# Ethernet-PHY.net
KiCad netlist of a schematic drawn in Altium Designer
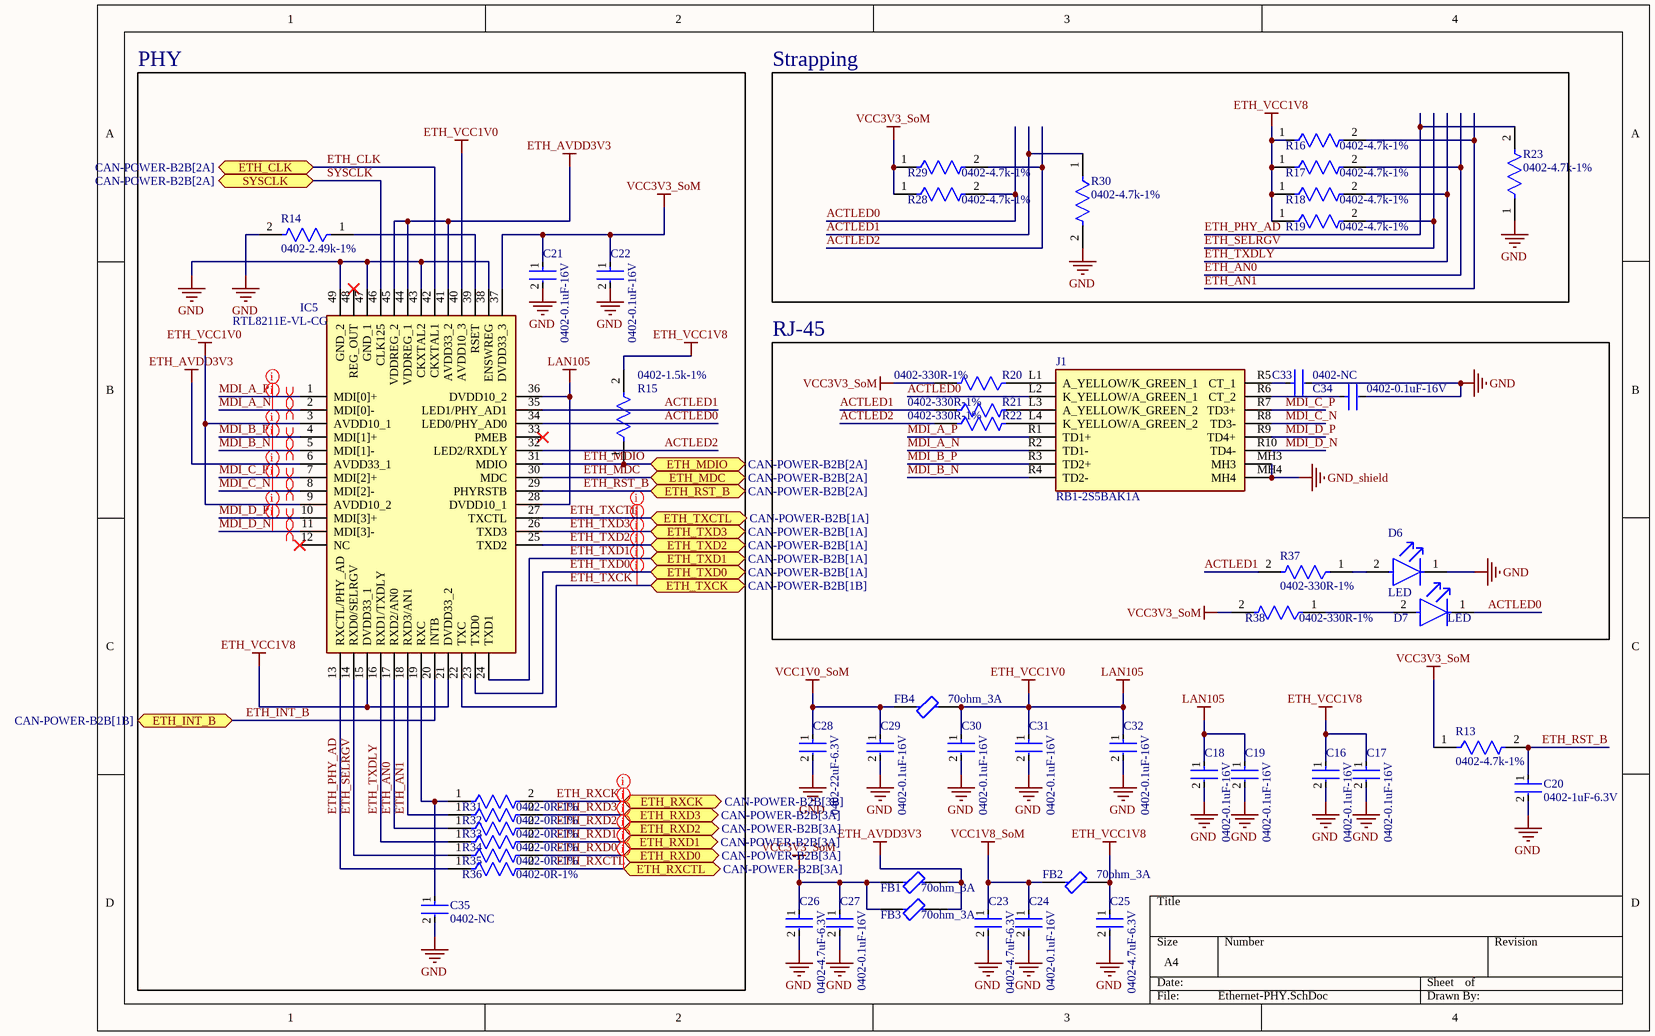
[diagram p0: Ethernet-PHY.SchDoc]

(export (version "E")
  (design (tool "Eeschema 10.0.6"))
  (components
    (comp (ref "C16")
      (value "0402-0.1uF-16V")
      (footprint "FP-GRM155-0_05-IPC_A")
      (description "CAP CER 0.22UF 10V X5R 0402")
      (fields (field (name "VOLTAGE") "10V") (field (name "TOLERANCE") "10%"))
      (libsource (lib "Altium Content Vault") (part "02cd4be3c70576c341d710602a673aa"))
    )
    (comp (ref "C17")
      (value "0402-0.1uF-16V")
      (footprint "FP-GRM155-0_05-IPC_A")
      (description "CAP CER 0.22UF 10V X5R 0402")
      (fields (field (name "VOLTAGE") "10V") (field (name "TOLERANCE") "10%"))
      (libsource (lib "Altium Content Vault") (part "02cd4be3c70576c341d710602a673aa"))
    )
    (comp (ref "C18")
      (value "0402-0.1uF-16V")
      (footprint "FP-GRM155-0_05-IPC_A")
      (description "CAP CER 0.22UF 10V X5R 0402")
      (fields (field (name "VOLTAGE") "10V") (field (name "TOLERANCE") "10%"))
      (libsource (lib "Altium Content Vault") (part "02cd4be3c70576c341d710602a673aa"))
    )
    (comp (ref "C19")
      (value "0402-0.1uF-16V")
      (footprint "FP-GRM155-0_05-IPC_A")
      (description "CAP CER 0.22UF 10V X5R 0402")
      (fields (field (name "VOLTAGE") "10V") (field (name "TOLERANCE") "10%"))
      (libsource (lib "Altium Content Vault") (part "02cd4be3c70576c341d710602a673aa"))
    )
    (comp (ref "C20")
      (value "0402-1uF-6.3V")
      (footprint "FP-GRM155-0_05-IPC_A")
      (description "CAP CER 0.22UF 10V X5R 0402")
      (fields (field (name "VOLTAGE") "10V") (field (name "TOLERANCE") "10%"))
      (libsource (lib "Altium Content Vault") (part "02cd4be3c70576c341d710602a673aa"))
    )
    (comp (ref "C21")
      (value "0402-0.1uF-16V")
      (footprint "FP-GRM155-0_05-IPC_A")
      (description "CAP CER 0.22UF 10V X5R 0402")
      (fields (field (name "VOLTAGE") "10V") (field (name "TOLERANCE") "10%"))
      (libsource (lib "Altium Content Vault") (part "02cd4be3c70576c341d710602a673aa"))
    )
    (comp (ref "C22")
      (value "0402-0.1uF-16V")
      (footprint "FP-GRM155-0_05-IPC_A")
      (description "CAP CER 0.22UF 10V X5R 0402")
      (fields (field (name "VOLTAGE") "10V") (field (name "TOLERANCE") "10%"))
      (libsource (lib "Altium Content Vault") (part "02cd4be3c70576c341d710602a673aa"))
    )
    (comp (ref "C23")
      (value "0402-4.7uF-6.3V")
      (footprint "FP-GRM155-0_05-IPC_A")
      (description "CAP CER 0.22UF 10V X5R 0402")
      (fields (field (name "VOLTAGE") "10V") (field (name "TOLERANCE") "10%"))
      (libsource (lib "Altium Content Vault") (part "02cd4be3c70576c341d710602a673aa"))
    )
    (comp (ref "C24")
      (value "0402-0.1uF-16V")
      (footprint "FP-GRM155-0_05-IPC_A")
      (description "CAP CER 0.22UF 10V X5R 0402")
      (fields (field (name "VOLTAGE") "10V") (field (name "TOLERANCE") "10%"))
      (libsource (lib "Altium Content Vault") (part "02cd4be3c70576c341d710602a673aa"))
    )
    (comp (ref "C25")
      (value "0402-4.7uF-6.3V")
      (footprint "FP-GRM155-0_05-IPC_A")
      (description "CAP CER 0.22UF 10V X5R 0402")
      (fields (field (name "VOLTAGE") "10V") (field (name "TOLERANCE") "10%"))
      (libsource (lib "Altium Content Vault") (part "02cd4be3c70576c341d710602a673aa"))
    )
    (comp (ref "C26")
      (value "0402-4.7uF-6.3V")
      (footprint "FP-GRM155-0_05-IPC_A")
      (description "CAP CER 0.22UF 10V X5R 0402")
      (fields (field (name "VOLTAGE") "10V") (field (name "TOLERANCE") "10%"))
      (libsource (lib "Altium Content Vault") (part "02cd4be3c70576c341d710602a673aa"))
    )
    (comp (ref "C27")
      (value "0402-0.1uF-16V")
      (footprint "FP-GRM155-0_05-IPC_A")
      (description "CAP CER 0.22UF 10V X5R 0402")
      (fields (field (name "VOLTAGE") "10V") (field (name "TOLERANCE") "10%"))
      (libsource (lib "Altium Content Vault") (part "02cd4be3c70576c341d710602a673aa"))
    )
    (comp (ref "C28")
      (value "0402-22uF-6.3V")
      (footprint "FP-GRM155-0_05-IPC_A")
      (description "CAP CER 0.22UF 10V X5R 0402")
      (fields (field (name "VOLTAGE") "10V") (field (name "TOLERANCE") "10%"))
      (libsource (lib "Altium Content Vault") (part "02cd4be3c70576c341d710602a673aa"))
    )
    (comp (ref "C29")
      (value "0402-0.1uF-16V")
      (footprint "FP-GRM155-0_05-IPC_A")
      (description "CAP CER 0.22UF 10V X5R 0402")
      (fields (field (name "VOLTAGE") "10V") (field (name "TOLERANCE") "10%"))
      (libsource (lib "Altium Content Vault") (part "02cd4be3c70576c341d710602a673aa"))
    )
    (comp (ref "C30")
      (value "0402-0.1uF-16V")
      (footprint "FP-GRM155-0_05-IPC_A")
      (description "CAP CER 0.22UF 10V X5R 0402")
      (fields (field (name "VOLTAGE") "10V") (field (name "TOLERANCE") "10%"))
      (libsource (lib "Altium Content Vault") (part "02cd4be3c70576c341d710602a673aa"))
    )
    (comp (ref "C31")
      (value "0402-0.1uF-16V")
      (footprint "FP-GRM155-0_05-IPC_A")
      (description "CAP CER 0.22UF 10V X5R 0402")
      (fields (field (name "VOLTAGE") "10V") (field (name "TOLERANCE") "10%"))
      (libsource (lib "Altium Content Vault") (part "02cd4be3c70576c341d710602a673aa"))
    )
    (comp (ref "C32")
      (value "0402-0.1uF-16V")
      (footprint "FP-GRM155-0_05-IPC_A")
      (description "CAP CER 0.22UF 10V X5R 0402")
      (fields (field (name "VOLTAGE") "10V") (field (name "TOLERANCE") "10%"))
      (libsource (lib "Altium Content Vault") (part "02cd4be3c70576c341d710602a673aa"))
    )
    (comp (ref "C33")
      (value "0402-NC")
      (footprint "FP-GRM155-0_05-IPC_A")
      (description "CAP CER 0.22UF 10V X5R 0402")
      (fields (field (name "VOLTAGE") "10V") (field (name "TOLERANCE") "10%"))
      (libsource (lib "") (part "02cd4be3c70576c341d710602a673aa_1"))
    )
    (comp (ref "C34")
      (value "0402-0.1uF-16V")
      (footprint "FP-GRM155-0_05-IPC_A")
      (description "CAP CER 0.22UF 10V X5R 0402")
      (fields (field (name "VOLTAGE") "10V") (field (name "TOLERANCE") "10%"))
      (libsource (lib "") (part "02cd4be3c70576c341d710602a673aa_1"))
    )
    (comp (ref "C35")
      (value "0402-NC")
      (footprint "FP-GRM155-0_05-IPC_A")
      (description "CAP CER 0.22UF 10V X5R 0402")
      (fields (field (name "VOLTAGE") "10V") (field (name "TOLERANCE") "10%"))
      (libsource (lib "Altium Content Vault") (part "02cd4be3c70576c341d710602a673aa"))
    )
    (comp (ref "D6")
      (value "LED")
      (footprint "FP-APHHS1005CGCK-MFG")
      (description "LED GREEN CLEAR CHIP SMD")
      (libsource (lib "Altium Content Vault") (part "8706943c75ba83719d021d2fdc84c58"))
    )
    (comp (ref "D7")
      (value "LED")
      (footprint "FP-APHHS1005CGCK-MFG")
      (description "LED GREEN CLEAR CHIP SMD")
      (libsource (lib "Altium Content Vault") (part "8706943c75ba83719d021d2fdc84c58"))
    )
    (comp (ref "FB1")
      (value "70ohm_3A")
      (footprint "FP-MPZ2012-MFG")
      (description "FERRITE BEAD 220 OHM 0805 1LN")
      (fields (field (name "TOLERANCE") "25%"))
      (libsource (lib "Altium Content Vault") (part "5f30dd21d616792df468990f7003faa"))
    )
    (comp (ref "FB2")
      (value "70ohm_3A")
      (footprint "FP-MPZ2012-MFG")
      (description "FERRITE BEAD 220 OHM 0805 1LN")
      (fields (field (name "TOLERANCE") "25%"))
      (libsource (lib "Altium Content Vault") (part "5f30dd21d616792df468990f7003faa"))
    )
    (comp (ref "FB3")
      (value "70ohm_3A")
      (footprint "FP-MPZ2012-MFG")
      (description "FERRITE BEAD 220 OHM 0805 1LN")
      (fields (field (name "TOLERANCE") "25%"))
      (libsource (lib "Altium Content Vault") (part "5f30dd21d616792df468990f7003faa"))
    )
    (comp (ref "FB4")
      (value "70ohm_3A")
      (footprint "FP-MPZ2012-MFG")
      (description "FERRITE BEAD 220 OHM 0805 1LN")
      (fields (field (name "TOLERANCE") "25%"))
      (libsource (lib "Altium Content Vault") (part "5f30dd21d616792df468990f7003faa"))
    )
    (comp (ref "IC5")
      (value "RTL8211E-VL-CG")
      (footprint "SamacSys:QFN40P600X600X100-49N")
      (description "Integrated Circuit")
      (libsource (lib "*") (part "RTL8211E-VL-CG"))
    )
    (comp (ref "J1")
      (value "RB1-2S5BAK1A")
      (footprint "SamacSys:RB12S5BAK1A")
      (description "Connector")
      (libsource (lib "*") (part "RB1-2S5BAK1A"))
    )
    (comp (ref "R13")
      (value "0402-4.7k-1%")
      (footprint "FP-CRCW0402-e3-IPC_C")
      (description "RES Thick Film, 0Ω, 0.063W, 0402")
      (fields (field (name "TOLERANCE") "5%"))
      (libsource (lib "Altium Content Vault") (part "1029c3af85768c4190bb7ad29bc67b5"))
    )
    (comp (ref "R14")
      (value "0402-2.49k-1%")
      (footprint "FP-CRCW0402-e3-IPC_C")
      (description "RES Thick Film, 0Ω, 0.063W, 0402")
      (fields (field (name "TOLERANCE") "5%"))
      (libsource (lib "Altium Content Vault") (part "1029c3af85768c4190bb7ad29bc67b5"))
    )
    (comp (ref "R15")
      (value "0402-1.5k-1%")
      (footprint "FP-CRCW0402-e3-IPC_C")
      (description "RES Thick Film, 0Ω, 0.063W, 0402")
      (fields (field (name "TOLERANCE") "5%"))
      (libsource (lib "Altium Content Vault") (part "1029c3af85768c4190bb7ad29bc67b5"))
    )
    (comp (ref "R16")
      (value "0402-4.7k-1%")
      (footprint "FP-CRCW0402-e3-IPC_C")
      (description "RES Thick Film, 0Ω, 0.063W, 0402")
      (fields (field (name "TOLERANCE") "5%"))
      (libsource (lib "Altium Content Vault") (part "1029c3af85768c4190bb7ad29bc67b5"))
    )
    (comp (ref "R17")
      (value "0402-4.7k-1%")
      (footprint "FP-CRCW0402-e3-IPC_C")
      (description "RES Thick Film, 0Ω, 0.063W, 0402")
      (fields (field (name "TOLERANCE") "5%"))
      (libsource (lib "Altium Content Vault") (part "1029c3af85768c4190bb7ad29bc67b5"))
    )
    (comp (ref "R18")
      (value "0402-4.7k-1%")
      (footprint "FP-CRCW0402-e3-IPC_C")
      (description "RES Thick Film, 0Ω, 0.063W, 0402")
      (fields (field (name "TOLERANCE") "5%"))
      (libsource (lib "Altium Content Vault") (part "1029c3af85768c4190bb7ad29bc67b5"))
    )
    (comp (ref "R19")
      (value "0402-4.7k-1%")
      (footprint "FP-CRCW0402-e3-IPC_C")
      (description "RES Thick Film, 0Ω, 0.063W, 0402")
      (fields (field (name "TOLERANCE") "5%"))
      (libsource (lib "Altium Content Vault") (part "1029c3af85768c4190bb7ad29bc67b5"))
    )
    (comp (ref "R20")
      (value "0402-330R-1%")
      (footprint "FP-CRCW0402-e3-IPC_C")
      (description "RES Thick Film, 0Ω, 0.063W, 0402")
      (fields (field (name "TOLERANCE") "5%"))
      (libsource (lib "") (part "1029c3af85768c4190bb7ad29bc67b5_1"))
    )
    (comp (ref "R21")
      (value "0402-330R-1%")
      (footprint "FP-CRCW0402-e3-IPC_C")
      (description "RES Thick Film, 0Ω, 0.063W, 0402")
      (fields (field (name "TOLERANCE") "5%"))
      (libsource (lib "") (part "1029c3af85768c4190bb7ad29bc67b5_1"))
    )
    (comp (ref "R22")
      (value "0402-330R-1%")
      (footprint "FP-CRCW0402-e3-IPC_C")
      (description "RES Thick Film, 0Ω, 0.063W, 0402")
      (fields (field (name "TOLERANCE") "5%"))
      (libsource (lib "") (part "1029c3af85768c4190bb7ad29bc67b5_1"))
    )
    (comp (ref "R23")
      (value "0402-4.7k-1%")
      (footprint "FP-CRCW0402-e3-IPC_C")
      (description "RES Thick Film, 0Ω, 0.063W, 0402")
      (fields (field (name "TOLERANCE") "5%"))
      (libsource (lib "Altium Content Vault") (part "1029c3af85768c4190bb7ad29bc67b5"))
    )
    (comp (ref "R28")
      (value "0402-4.7k-1%")
      (footprint "FP-CRCW0402-e3-IPC_C")
      (description "RES Thick Film, 0Ω, 0.063W, 0402")
      (fields (field (name "TOLERANCE") "5%"))
      (libsource (lib "Altium Content Vault") (part "1029c3af85768c4190bb7ad29bc67b5"))
    )
    (comp (ref "R29")
      (value "0402-4.7k-1%")
      (footprint "FP-CRCW0402-e3-IPC_C")
      (description "RES Thick Film, 0Ω, 0.063W, 0402")
      (fields (field (name "TOLERANCE") "5%"))
      (libsource (lib "Altium Content Vault") (part "1029c3af85768c4190bb7ad29bc67b5"))
    )
    (comp (ref "R30")
      (value "0402-4.7k-1%")
      (footprint "FP-CRCW0402-e3-IPC_C")
      (description "RES Thick Film, 0Ω, 0.063W, 0402")
      (fields (field (name "TOLERANCE") "5%"))
      (libsource (lib "Altium Content Vault") (part "1029c3af85768c4190bb7ad29bc67b5"))
    )
    (comp (ref "R31")
      (value "0402-0R-1%")
      (footprint "FP-CRCW0402-e3-IPC_C")
      (description "RES Thick Film, 0Ω, 0.063W, 0402")
      (fields (field (name "TOLERANCE") "5%"))
      (libsource (lib "Altium Content Vault") (part "1029c3af85768c4190bb7ad29bc67b5"))
    )
    (comp (ref "R32")
      (value "0402-0R-1%")
      (footprint "FP-CRCW0402-e3-IPC_C")
      (description "RES Thick Film, 0Ω, 0.063W, 0402")
      (fields (field (name "TOLERANCE") "5%"))
      (libsource (lib "Altium Content Vault") (part "1029c3af85768c4190bb7ad29bc67b5"))
    )
    (comp (ref "R33")
      (value "0402-0R-1%")
      (footprint "FP-CRCW0402-e3-IPC_C")
      (description "RES Thick Film, 0Ω, 0.063W, 0402")
      (fields (field (name "TOLERANCE") "5%"))
      (libsource (lib "Altium Content Vault") (part "1029c3af85768c4190bb7ad29bc67b5"))
    )
    (comp (ref "R34")
      (value "0402-0R-1%")
      (footprint "FP-CRCW0402-e3-IPC_C")
      (description "RES Thick Film, 0Ω, 0.063W, 0402")
      (fields (field (name "TOLERANCE") "5%"))
      (libsource (lib "Altium Content Vault") (part "1029c3af85768c4190bb7ad29bc67b5"))
    )
    (comp (ref "R35")
      (value "0402-0R-1%")
      (footprint "FP-CRCW0402-e3-IPC_C")
      (description "RES Thick Film, 0Ω, 0.063W, 0402")
      (fields (field (name "TOLERANCE") "5%"))
      (libsource (lib "Altium Content Vault") (part "1029c3af85768c4190bb7ad29bc67b5"))
    )
    (comp (ref "R36")
      (value "0402-0R-1%")
      (footprint "FP-CRCW0402-e3-IPC_C")
      (description "RES Thick Film, 0Ω, 0.063W, 0402")
      (fields (field (name "TOLERANCE") "5%"))
      (libsource (lib "Altium Content Vault") (part "1029c3af85768c4190bb7ad29bc67b5"))
    )
    (comp (ref "R37")
      (value "0402-330R-1%")
      (footprint "FP-CRCW0402-e3-IPC_C")
      (description "RES Thick Film, 0Ω, 0.063W, 0402")
      (fields (field (name "TOLERANCE") "5%"))
      (libsource (lib "Altium Content Vault") (part "1029c3af85768c4190bb7ad29bc67b5"))
    )
    (comp (ref "R38")
      (value "0402-330R-1%")
      (footprint "FP-CRCW0402-e3-IPC_C")
      (description "RES Thick Film, 0Ω, 0.063W, 0402")
      (fields (field (name "TOLERANCE") "5%"))
      (libsource (lib "Altium Content Vault") (part "1029c3af85768c4190bb7ad29bc67b5"))
    )
  )
  (nets
    (net (code "1") (name "/ACTLED0") (class "Default")
      (node (ref "D7") (pin "1") (pinfunction "C_1") (pintype "passive"))
      (node (ref "IC5") (pin "34") (pinfunction "LED0/PHY_AD0_34") (pintype "passive"))
      (node (ref "J1") (pin "L2") (pinfunction "K_YELLOW/A_GREEN_1_L2") (pintype "passive"))
      (node (ref "R28") (pin "2") (pinfunction "2_2") (pintype "passive"))
    )
    (net (code "2") (name "/ACTLED1") (class "Default")
      (node (ref "IC5") (pin "35") (pinfunction "LED1/PHY_AD1_35") (pintype "passive"))
      (node (ref "R21") (pin "1") (pinfunction "1_1") (pintype "passive"))
      (node (ref "R30") (pin "1") (pinfunction "1_1") (pintype "passive"))
      (node (ref "R37") (pin "2") (pinfunction "2_2") (pintype "passive"))
    )
    (net (code "3") (name "/ACTLED2") (class "Default")
      (node (ref "IC5") (pin "32") (pinfunction "LED2/RXDLY_32") (pintype "passive"))
      (node (ref "R22") (pin "1") (pinfunction "1_1") (pintype "passive"))
      (node (ref "R29") (pin "2") (pinfunction "2_2") (pintype "passive"))
    )
    (net (code "4") (name "/ETH_AN0") (class "Default")
      (node (ref "IC5") (pin "17") (pinfunction "RXD2/AN0_17") (pintype "passive"))
      (node (ref "R17") (pin "2") (pinfunction "2_2") (pintype "passive"))
      (node (ref "R33") (pin "1") (pinfunction "1_1") (pintype "passive"))
    )
    (net (code "5") (name "/ETH_AN1") (class "Default")
      (node (ref "IC5") (pin "18") (pinfunction "RXD3/AN1_18") (pintype "passive"))
      (node (ref "R16") (pin "2") (pinfunction "2_2") (pintype "passive"))
      (node (ref "R32") (pin "1") (pinfunction "1_1") (pintype "passive"))
    )
    (net (code "6") (name "/ETH_CLK") (class "Default")
      (node (ref "IC5") (pin "42") (pinfunction "CKXTAL1_42") (pintype "passive"))
    )
    (net (code "7") (name "/ETH_INT_B") (class "Default")
      (node (ref "IC5") (pin "20") (pinfunction "INTB_20") (pintype "passive"))
    )
    (net (code "8") (name "/ETH_MDC") (class "Default")
      (node (ref "IC5") (pin "30") (pinfunction "MDC_30") (pintype "passive"))
    )
    (net (code "9") (name "/ETH_MDIO") (class "Default")
      (node (ref "IC5") (pin "31") (pinfunction "MDIO_31") (pintype "passive"))
      (node (ref "R15") (pin "1") (pinfunction "1_1") (pintype "passive"))
    )
    (net (code "10") (name "/ETH_PHY_AD") (class "Default")
      (node (ref "IC5") (pin "13") (pinfunction "RXCTL/PHY_AD_13") (pintype "passive"))
      (node (ref "R23") (pin "2") (pinfunction "2_2") (pintype "passive"))
      (node (ref "R36") (pin "1") (pinfunction "1_1") (pintype "passive"))
    )
    (net (code "11") (name "/ETH_RST_B") (class "Default")
      (node (ref "C20") (pin "1") (pinfunction "1_1") (pintype "passive"))
      (node (ref "IC5") (pin "29") (pinfunction "PHYRSTB_29") (pintype "passive"))
      (node (ref "R13") (pin "2") (pinfunction "2_2") (pintype "passive"))
    )
    (net (code "12") (name "/ETH_RXCK") (class "Default")
      (node (ref "R31") (pin "2") (pinfunction "2_2") (pintype "passive"))
    )
    (net (code "13") (name "/ETH_RXCTL") (class "Default")
      (node (ref "R36") (pin "2") (pinfunction "2_2") (pintype "passive"))
    )
    (net (code "14") (name "/ETH_RXD0") (class "Default")
      (node (ref "R35") (pin "2") (pinfunction "2_2") (pintype "passive"))
    )
    (net (code "15") (name "/ETH_RXD1") (class "Default")
      (node (ref "R34") (pin "2") (pinfunction "2_2") (pintype "passive"))
    )
    (net (code "16") (name "/ETH_RXD2") (class "Default")
      (node (ref "R33") (pin "2") (pinfunction "2_2") (pintype "passive"))
    )
    (net (code "17") (name "/ETH_RXD3") (class "Default")
      (node (ref "R32") (pin "2") (pinfunction "2_2") (pintype "passive"))
    )
    (net (code "18") (name "/ETH_SELRGV") (class "Default")
      (node (ref "IC5") (pin "14") (pinfunction "RXD0/SELRGV_14") (pintype "passive"))
      (node (ref "R19") (pin "2") (pinfunction "2_2") (pintype "passive"))
      (node (ref "R35") (pin "1") (pinfunction "1_1") (pintype "passive"))
    )
    (net (code "19") (name "/ETH_TXCK") (class "Default")
      (node (ref "IC5") (pin "22") (pinfunction "TXC_22") (pintype "passive"))
    )
    (net (code "20") (name "/ETH_TXCTL") (class "Default")
      (node (ref "IC5") (pin "27") (pinfunction "TXCTL_27") (pintype "passive"))
    )
    (net (code "21") (name "/ETH_TXD0") (class "Default")
      (node (ref "IC5") (pin "23") (pinfunction "TXD0_23") (pintype "passive"))
    )
    (net (code "22") (name "/ETH_TXD1") (class "Default")
      (node (ref "IC5") (pin "24") (pinfunction "TXD1_24") (pintype "passive"))
    )
    (net (code "23") (name "/ETH_TXD2") (class "Default")
      (node (ref "IC5") (pin "25") (pinfunction "TXD2_25") (pintype "passive"))
    )
    (net (code "24") (name "/ETH_TXD3") (class "Default")
      (node (ref "IC5") (pin "26") (pinfunction "TXD3_26") (pintype "passive"))
    )
    (net (code "25") (name "/ETH_TXDLY") (class "Default")
      (node (ref "IC5") (pin "16") (pinfunction "RXD1/TXDLY_16") (pintype "passive"))
      (node (ref "R18") (pin "2") (pinfunction "2_2") (pintype "passive"))
      (node (ref "R34") (pin "1") (pinfunction "1_1") (pintype "passive"))
    )
    (net (code "26") (name "/MDI_A_N") (class "Default")
      (node (ref "IC5") (pin "2") (pinfunction "MDI[0]-_2") (pintype "passive"))
      (node (ref "J1") (pin "R2") (pinfunction "TD1-_R2") (pintype "passive"))
    )
    (net (code "27") (name "/MDI_A_P") (class "Default")
      (node (ref "IC5") (pin "1") (pinfunction "MDI[0]+_1") (pintype "passive"))
      (node (ref "J1") (pin "R1") (pinfunction "TD1+_R1") (pintype "passive"))
    )
    (net (code "28") (name "/MDI_B_N") (class "Default")
      (node (ref "IC5") (pin "5") (pinfunction "MDI[1]-_5") (pintype "passive"))
      (node (ref "J1") (pin "R4") (pinfunction "TD2-_R4") (pintype "passive"))
    )
    (net (code "29") (name "/MDI_B_P") (class "Default")
      (node (ref "IC5") (pin "4") (pinfunction "MDI[1]+_4") (pintype "passive"))
      (node (ref "J1") (pin "R3") (pinfunction "TD2+_R3") (pintype "passive"))
    )
    (net (code "30") (name "/MDI_C_N") (class "Default")
      (node (ref "IC5") (pin "8") (pinfunction "MDI[2]-_8") (pintype "passive"))
      (node (ref "J1") (pin "R8") (pinfunction "TD3-_R8") (pintype "passive"))
    )
    (net (code "31") (name "/MDI_C_P") (class "Default")
      (node (ref "IC5") (pin "7") (pinfunction "MDI[2]+_7") (pintype "passive"))
      (node (ref "J1") (pin "R7") (pinfunction "TD3+_R7") (pintype "passive"))
    )
    (net (code "32") (name "/MDI_D_N") (class "Default")
      (node (ref "IC5") (pin "11") (pinfunction "MDI[3]-_11") (pintype "passive"))
      (node (ref "J1") (pin "R10") (pinfunction "TD4-_R10") (pintype "passive"))
    )
    (net (code "33") (name "/MDI_D_P") (class "Default")
      (node (ref "IC5") (pin "10") (pinfunction "MDI[3]+_10") (pintype "passive"))
      (node (ref "J1") (pin "R9") (pinfunction "TD4+_R9") (pintype "passive"))
    )
    (net (code "34") (name "/SYSCLK") (class "Default")
      (node (ref "IC5") (pin "46") (pinfunction "CLK125_46") (pintype "passive"))
    )
    (net (code "35") (name "ETH_AVDD3V3") (class "Default")
      (node (ref "FB1") (pin "2") (pinfunction "2_2") (pintype "passive"))
      (node (ref "FB3") (pin "2") (pinfunction "2_2") (pintype "passive"))
      (node (ref "IC5") (pin "41") (pinfunction "AVDD33_2_41") (pintype "passive"))
      (node (ref "IC5") (pin "44") (pinfunction "VDDREG_1_44") (pintype "passive"))
      (node (ref "IC5") (pin "45") (pinfunction "VDDREG_2_45") (pintype "passive"))
      (node (ref "IC5") (pin "6") (pinfunction "AVDD33_1_6") (pintype "passive"))
    )
    (net (code "36") (name "ETH_VCC1V0") (class "Default")
      (node (ref "C18") (pin "1") (pinfunction "1_1") (pintype "passive"))
      (node (ref "C19") (pin "1") (pinfunction "1_1") (pintype "passive"))
      (node (ref "C30") (pin "1") (pinfunction "1_1") (pintype "passive"))
      (node (ref "C31") (pin "1") (pinfunction "1_1") (pintype "passive"))
      (node (ref "C32") (pin "1") (pinfunction "1_1") (pintype "passive"))
      (node (ref "FB4") (pin "2") (pinfunction "2_2") (pintype "passive"))
      (node (ref "IC5") (pin "28") (pinfunction "DVDD10_1_28") (pintype "passive"))
      (node (ref "IC5") (pin "3") (pinfunction "AVDD10_1_3") (pintype "passive"))
      (node (ref "IC5") (pin "36") (pinfunction "DVDD10_2_36") (pintype "passive"))
      (node (ref "IC5") (pin "40") (pinfunction "AVDD10_3_40") (pintype "passive"))
      (node (ref "IC5") (pin "9") (pinfunction "AVDD10_2_9") (pintype "passive"))
    )
    (net (code "37") (name "ETH_VCC1V8") (class "Default")
      (node (ref "C16") (pin "1") (pinfunction "1_1") (pintype "passive"))
      (node (ref "C17") (pin "1") (pinfunction "1_1") (pintype "passive"))
      (node (ref "C25") (pin "1") (pinfunction "1_1") (pintype "passive"))
      (node (ref "FB2") (pin "2") (pinfunction "2_2") (pintype "passive"))
      (node (ref "IC5") (pin "15") (pinfunction "DVDD33_1_15") (pintype "passive"))
      (node (ref "IC5") (pin "21") (pinfunction "DVDD33_2_21") (pintype "passive"))
      (node (ref "R15") (pin "2") (pinfunction "2_2") (pintype "passive"))
      (node (ref "R16") (pin "1") (pinfunction "1_1") (pintype "passive"))
      (node (ref "R17") (pin "1") (pinfunction "1_1") (pintype "passive"))
      (node (ref "R18") (pin "1") (pinfunction "1_1") (pintype "passive"))
      (node (ref "R19") (pin "1") (pinfunction "1_1") (pintype "passive"))
    )
    (net (code "38") (name "GND") (class "Default")
      (node (ref "C16") (pin "2") (pinfunction "2_2") (pintype "passive"))
      (node (ref "C17") (pin "2") (pinfunction "2_2") (pintype "passive"))
      (node (ref "C18") (pin "2") (pinfunction "2_2") (pintype "passive"))
      (node (ref "C19") (pin "2") (pinfunction "2_2") (pintype "passive"))
      (node (ref "C20") (pin "2") (pinfunction "2_2") (pintype "passive"))
      (node (ref "C21") (pin "2") (pinfunction "2_2") (pintype "passive"))
      (node (ref "C22") (pin "2") (pinfunction "2_2") (pintype "passive"))
      (node (ref "C23") (pin "2") (pinfunction "2_2") (pintype "passive"))
      (node (ref "C24") (pin "2") (pinfunction "2_2") (pintype "passive"))
      (node (ref "C25") (pin "2") (pinfunction "2_2") (pintype "passive"))
      (node (ref "C26") (pin "2") (pinfunction "2_2") (pintype "passive"))
      (node (ref "C27") (pin "2") (pinfunction "2_2") (pintype "passive"))
      (node (ref "C28") (pin "2") (pinfunction "2_2") (pintype "passive"))
      (node (ref "C29") (pin "2") (pinfunction "2_2") (pintype "passive"))
      (node (ref "C30") (pin "2") (pinfunction "2_2") (pintype "passive"))
      (node (ref "C31") (pin "2") (pinfunction "2_2") (pintype "passive"))
      (node (ref "C32") (pin "2") (pinfunction "2_2") (pintype "passive"))
      (node (ref "C33") (pin "2") (pinfunction "2_2") (pintype "passive"))
      (node (ref "C34") (pin "2") (pinfunction "2_2") (pintype "passive"))
      (node (ref "C35") (pin "2") (pinfunction "2_2") (pintype "passive"))
      (node (ref "D6") (pin "1") (pinfunction "C_1") (pintype "passive"))
      (node (ref "IC5") (pin "38") (pinfunction "ENSWREG_38") (pintype "passive"))
      (node (ref "IC5") (pin "43") (pinfunction "CKXTAL2_43") (pintype "passive"))
      (node (ref "IC5") (pin "47") (pinfunction "GND_1_47") (pintype "passive"))
      (node (ref "IC5") (pin "49") (pinfunction "GND_2_49") (pintype "passive"))
      (node (ref "R14") (pin "2") (pinfunction "2_2") (pintype "passive"))
      (node (ref "R23") (pin "1") (pinfunction "1_1") (pintype "passive"))
      (node (ref "R30") (pin "2") (pinfunction "2_2") (pintype "passive"))
    )
    (net (code "39") (name "GND_shield") (class "Default")
      (node (ref "J1") (pin "MH3") (pinfunction "MH3_MH3") (pintype "passive"))
      (node (ref "J1") (pin "MH4") (pinfunction "MH4_MH4") (pintype "passive"))
    )
    (net (code "40") (name "Net-(D6-A)") (class "Default")
      (node (ref "D6") (pin "2") (pinfunction "A_2") (pintype "passive"))
      (node (ref "R37") (pin "1") (pinfunction "1_1") (pintype "passive"))
    )
    (net (code "41") (name "Net-(D7-A)") (class "Default")
      (node (ref "D7") (pin "2") (pinfunction "A_2") (pintype "passive"))
      (node (ref "R38") (pin "1") (pinfunction "1_1") (pintype "passive"))
    )
    (net (code "42") (name "Net-(IC5-RSET)") (class "Default")
      (node (ref "IC5") (pin "39") (pinfunction "RSET_39") (pintype "passive"))
      (node (ref "R14") (pin "1") (pinfunction "1_1") (pintype "passive"))
    )
    (net (code "43") (name "Net-(IC5-RXC)") (class "Default")
      (node (ref "C35") (pin "1") (pinfunction "1_1") (pintype "passive"))
      (node (ref "IC5") (pin "19") (pinfunction "RXC_19") (pintype "passive"))
      (node (ref "R31") (pin "1") (pinfunction "1_1") (pintype "passive"))
    )
    (net (code "44") (name "Net-(J1-A_YELLOW{slash}K_GREEN_1)") (class "Default")
      (node (ref "J1") (pin "L1") (pinfunction "A_YELLOW/K_GREEN_1_L1") (pintype "passive"))
      (node (ref "R20") (pin "1") (pinfunction "1_1") (pintype "passive"))
    )
    (net (code "45") (name "Net-(J1-A_YELLOW{slash}K_GREEN_2)") (class "Default")
      (node (ref "J1") (pin "L3") (pinfunction "A_YELLOW/K_GREEN_2_L3") (pintype "passive"))
      (node (ref "R21") (pin "2") (pinfunction "2_2") (pintype "passive"))
    )
    (net (code "46") (name "Net-(J1-CT_1)") (class "Default")
      (node (ref "C33") (pin "1") (pinfunction "1_1") (pintype "passive"))
      (node (ref "J1") (pin "R5") (pinfunction "CT_1_R5") (pintype "passive"))
    )
    (net (code "47") (name "Net-(J1-CT_2)") (class "Default")
      (node (ref "C34") (pin "1") (pinfunction "1_1") (pintype "passive"))
      (node (ref "J1") (pin "R6") (pinfunction "CT_2_R6") (pintype "passive"))
    )
    (net (code "48") (name "Net-(J1-K_YELLOW{slash}A_GREEN_2)") (class "Default")
      (node (ref "J1") (pin "L4") (pinfunction "K_YELLOW/A_GREEN_2_L4") (pintype "passive"))
      (node (ref "R22") (pin "2") (pinfunction "2_2") (pintype "passive"))
    )
    (net (code "49") (name "VCC1V0_SoM") (class "Default")
      (node (ref "C28") (pin "1") (pinfunction "1_1") (pintype "passive"))
      (node (ref "C29") (pin "1") (pinfunction "1_1") (pintype "passive"))
      (node (ref "FB4") (pin "1") (pinfunction "1_1") (pintype "passive"))
    )
    (net (code "50") (name "VCC1V8_SoM") (class "Default")
      (node (ref "C23") (pin "1") (pinfunction "1_1") (pintype "passive"))
      (node (ref "C24") (pin "1") (pinfunction "1_1") (pintype "passive"))
      (node (ref "FB2") (pin "1") (pinfunction "1_1") (pintype "passive"))
    )
    (net (code "51") (name "VCC3V3_SoM") (class "Default")
      (node (ref "C21") (pin "1") (pinfunction "1_1") (pintype "passive"))
      (node (ref "C22") (pin "1") (pinfunction "1_1") (pintype "passive"))
      (node (ref "C26") (pin "1") (pinfunction "1_1") (pintype "passive"))
      (node (ref "C27") (pin "1") (pinfunction "1_1") (pintype "passive"))
      (node (ref "FB1") (pin "1") (pinfunction "1_1") (pintype "passive"))
      (node (ref "FB3") (pin "1") (pinfunction "1_1") (pintype "passive"))
      (node (ref "IC5") (pin "37") (pinfunction "DVDD33_3_37") (pintype "passive"))
      (node (ref "R13") (pin "1") (pinfunction "1_1") (pintype "passive"))
      (node (ref "R20") (pin "2") (pinfunction "2_2") (pintype "passive"))
      (node (ref "R28") (pin "1") (pinfunction "1_1") (pintype "passive"))
      (node (ref "R29") (pin "1") (pinfunction "1_1") (pintype "passive"))
      (node (ref "R38") (pin "2") (pinfunction "2_2") (pintype "passive"))
    )
    (net (code "52") (name "unconnected-(IC5-NC-Pad12)") (class "Default")
      (node (ref "IC5") (pin "12") (pinfunction "NC_12") (pintype "passive+no_connect"))
    )
    (net (code "53") (name "unconnected-(IC5-PMEB-Pad33)") (class "Default")
      (node (ref "IC5") (pin "33") (pinfunction "PMEB_33") (pintype "passive+no_connect"))
    )
    (net (code "54") (name "unconnected-(IC5-REG_OUT-Pad48)") (class "Default")
      (node (ref "IC5") (pin "48") (pinfunction "REG_OUT_48") (pintype "passive+no_connect"))
    )
  )
)
